# Gigabit_Ethernet.net
KiCad netlist of a schematic drawn in Altium Designer
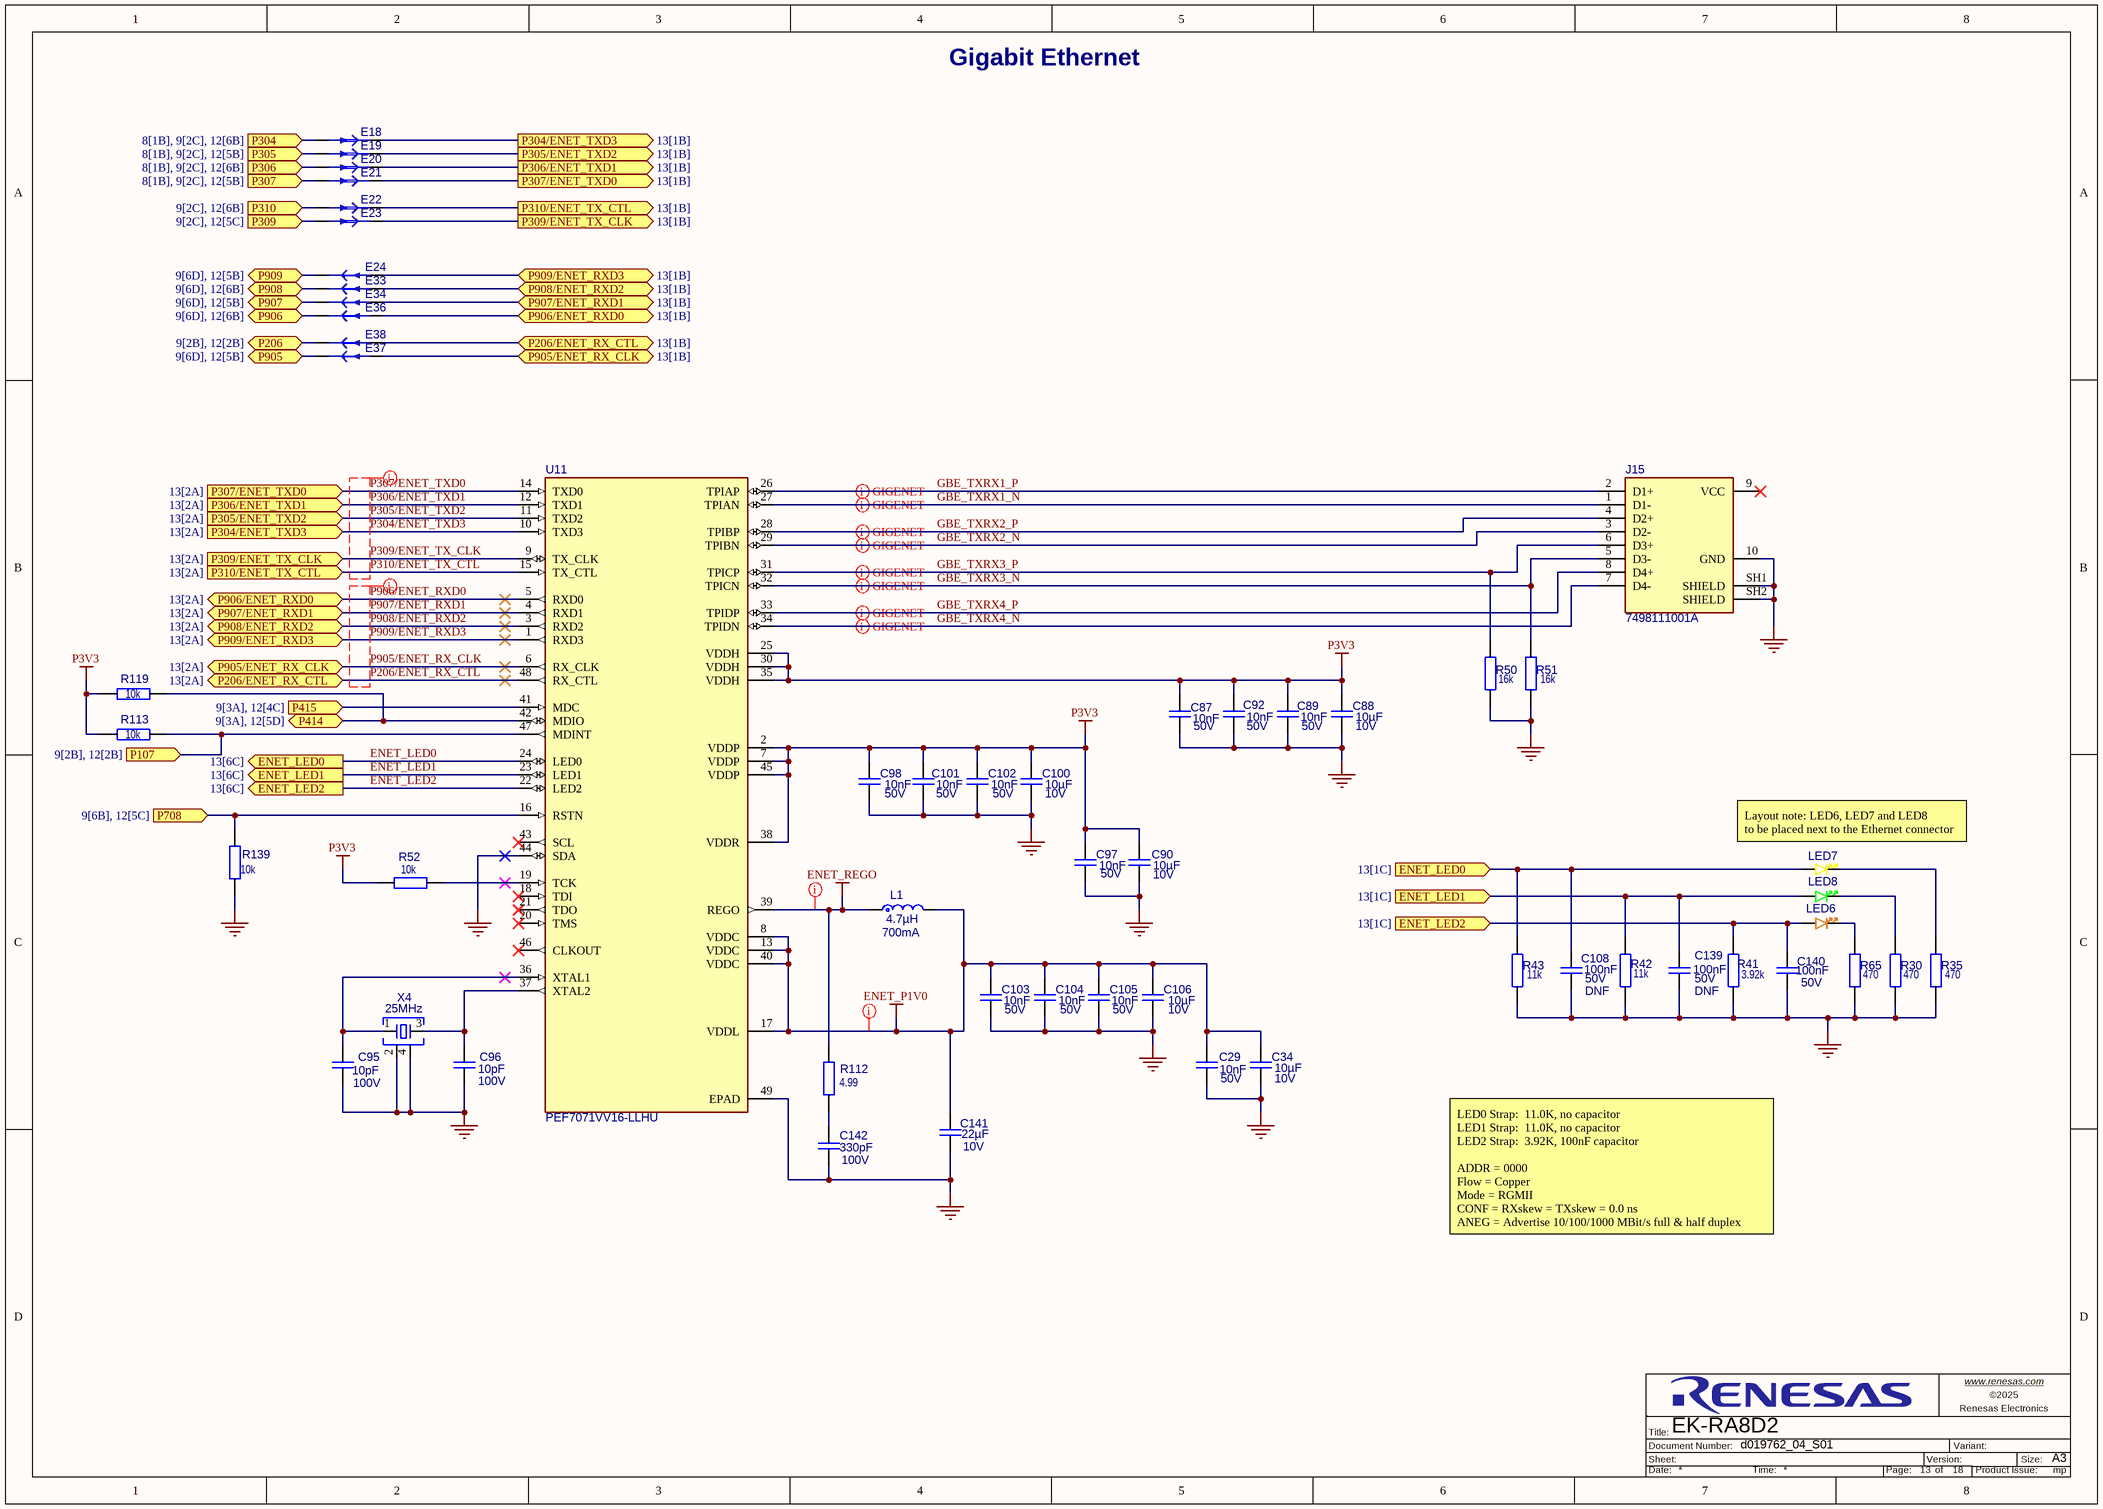
[diagram p0: Gigabit Ethernet.SchDoc]

(export (version "E")
  (design (tool "Eeschema 10.0.6"))
  (components
    (comp (ref "C29")
      (value "10nF")
      (footprint "C_EIA0402_0p55")
      (description "Capacitor,EIA0402,10n,50V,X7R")
      (fields
        (field (name "TOLERANCE") "10%")
        (field (name "OPERATING VOLTAGE MAX") "50V")
        (field (name "Comment") "Capacitor")
      )
      (libsource (lib "ek-ra8d2_mp - Customer") (part "Capacitor"))
    )
    (comp (ref "C34")
      (value "10µF")
      (footprint "C_EIA0402_0p7")
      (description "Capacitor,EIA0402,10u,10V,X5R")
      (fields
        (field (name "TOLERANCE") "20%")
        (field (name "OPERATING VOLTAGE MAX") "10V")
        (field (name "Comment") "Capacitor")
      )
      (libsource (lib "ek-ra8d2_mp - Customer") (part "Capacitor"))
    )
    (comp (ref "C87")
      (value "10nF")
      (footprint "C_EIA0402_0p55")
      (description "Capacitor,EIA0402,10n,50V,X7R")
      (fields
        (field (name "TOLERANCE") "10%")
        (field (name "OPERATING VOLTAGE MAX") "50V")
        (field (name "Comment") "Capacitor")
      )
      (libsource (lib "ek-ra8d2_mp - Customer") (part "Capacitor"))
    )
    (comp (ref "C88")
      (value "10µF")
      (footprint "C_EIA0402_0p7")
      (description "Capacitor,EIA0402,10u,10V,X5R")
      (fields
        (field (name "TOLERANCE") "20%")
        (field (name "OPERATING VOLTAGE MAX") "10V")
        (field (name "Comment") "Capacitor")
      )
      (libsource (lib "ek-ra8d2_mp - Customer") (part "Capacitor"))
    )
    (comp (ref "C89")
      (value "10nF")
      (footprint "C_EIA0402_0p55")
      (description "Capacitor,EIA0402,10n,50V,X7R")
      (fields
        (field (name "TOLERANCE") "10%")
        (field (name "OPERATING VOLTAGE MAX") "50V")
        (field (name "Comment") "Capacitor")
      )
      (libsource (lib "ek-ra8d2_mp - Customer") (part "Capacitor"))
    )
    (comp (ref "C90")
      (value "10µF")
      (footprint "C_EIA0402_0p7")
      (description "Capacitor,EIA0402,10u,10V,X5R")
      (fields
        (field (name "TOLERANCE") "20%")
        (field (name "OPERATING VOLTAGE MAX") "10V")
        (field (name "Comment") "Capacitor")
      )
      (libsource (lib "ek-ra8d2_mp - Customer") (part "Capacitor"))
    )
    (comp (ref "C92")
      (value "10nF")
      (footprint "C_EIA0402_0p55")
      (description "Capacitor,EIA0402,10n,50V,X7R")
      (fields
        (field (name "TOLERANCE") "10%")
        (field (name "OPERATING VOLTAGE MAX") "50V")
        (field (name "Comment") "Capacitor")
      )
      (libsource (lib "ek-ra8d2_mp - Customer") (part "Capacitor"))
    )
    (comp (ref "C95")
      (value "10pF")
      (footprint "C_EIA0402_0p55")
      (description "Capacitor,EIA0402,10p,100V,C0G")
      (fields
        (field (name "TOLERANCE") "5%")
        (field (name "OPERATING VOLTAGE MAX") "100V")
        (field (name "Comment") "Capacitor")
      )
      (libsource (lib "ek-ra8d2_mp - Customer") (part "Capacitor"))
    )
    (comp (ref "C96")
      (value "10pF")
      (footprint "C_EIA0402_0p55")
      (description "Capacitor,EIA0402,10p,100V,C0G")
      (fields
        (field (name "TOLERANCE") "5%")
        (field (name "OPERATING VOLTAGE MAX") "100V")
        (field (name "Comment") "Capacitor")
      )
      (libsource (lib "ek-ra8d2_mp - Customer") (part "Capacitor"))
    )
    (comp (ref "C97")
      (value "10nF")
      (footprint "C_EIA0402_0p55")
      (description "Capacitor,EIA0402,10n,50V,X7R")
      (fields
        (field (name "TOLERANCE") "10%")
        (field (name "OPERATING VOLTAGE MAX") "50V")
        (field (name "Comment") "Capacitor")
      )
      (libsource (lib "ek-ra8d2_mp - Customer") (part "Capacitor"))
    )
    (comp (ref "C98")
      (value "10nF")
      (footprint "C_EIA0402_0p55")
      (description "Capacitor,EIA0402,10n,50V,X7R")
      (fields
        (field (name "TOLERANCE") "10%")
        (field (name "OPERATING VOLTAGE MAX") "50V")
        (field (name "Comment") "Capacitor")
      )
      (libsource (lib "ek-ra8d2_mp - Customer") (part "Capacitor"))
    )
    (comp (ref "C100")
      (value "10µF")
      (footprint "C_EIA0402_0p7")
      (description "Capacitor,EIA0402,10u,10V,X5R")
      (fields
        (field (name "TOLERANCE") "20%")
        (field (name "OPERATING VOLTAGE MAX") "10V")
        (field (name "Comment") "Capacitor")
      )
      (libsource (lib "ek-ra8d2_mp - Customer") (part "Capacitor"))
    )
    (comp (ref "C101")
      (value "10nF")
      (footprint "C_EIA0402_0p55")
      (description "Capacitor,EIA0402,10n,50V,X7R")
      (fields
        (field (name "TOLERANCE") "10%")
        (field (name "OPERATING VOLTAGE MAX") "50V")
        (field (name "Comment") "Capacitor")
      )
      (libsource (lib "ek-ra8d2_mp - Customer") (part "Capacitor"))
    )
    (comp (ref "C102")
      (value "10nF")
      (footprint "C_EIA0402_0p55")
      (description "Capacitor,EIA0402,10n,50V,X7R")
      (fields
        (field (name "TOLERANCE") "10%")
        (field (name "OPERATING VOLTAGE MAX") "50V")
        (field (name "Comment") "Capacitor")
      )
      (libsource (lib "ek-ra8d2_mp - Customer") (part "Capacitor"))
    )
    (comp (ref "C103")
      (value "10nF")
      (footprint "C_EIA0402_0p55")
      (description "Capacitor,EIA0402,10n,50V,X7R")
      (fields
        (field (name "TOLERANCE") "10%")
        (field (name "OPERATING VOLTAGE MAX") "50V")
        (field (name "Comment") "Capacitor")
      )
      (libsource (lib "ek-ra8d2_mp - Customer") (part "Capacitor"))
    )
    (comp (ref "C104")
      (value "10nF")
      (footprint "C_EIA0402_0p55")
      (description "Capacitor,EIA0402,10n,50V,X7R")
      (fields
        (field (name "TOLERANCE") "10%")
        (field (name "OPERATING VOLTAGE MAX") "50V")
        (field (name "Comment") "Capacitor")
      )
      (libsource (lib "ek-ra8d2_mp - Customer") (part "Capacitor"))
    )
    (comp (ref "C105")
      (value "10nF")
      (footprint "C_EIA0402_0p55")
      (description "Capacitor,EIA0402,10n,50V,X7R")
      (fields
        (field (name "TOLERANCE") "10%")
        (field (name "OPERATING VOLTAGE MAX") "50V")
        (field (name "Comment") "Capacitor")
      )
      (libsource (lib "ek-ra8d2_mp - Customer") (part "Capacitor"))
    )
    (comp (ref "C106")
      (value "10µF")
      (footprint "C_EIA0402_0p7")
      (description "Capacitor,EIA0402,10u,10V,X5R")
      (fields
        (field (name "TOLERANCE") "20%")
        (field (name "OPERATING VOLTAGE MAX") "10V")
        (field (name "Comment") "Capacitor")
      )
      (libsource (lib "ek-ra8d2_mp - Customer") (part "Capacitor"))
    )
    (comp (ref "C108")
      (value "100nF")
      (footprint "C_EIA0402_0p55")
      (description "Capacitor,EIA0402,100n,50V,X7R")
      (fields
        (field (name "TOLERANCE") "10%")
        (field (name "OPERATING VOLTAGE MAX") "50V")
        (field (name "DNF") "DNF")
        (field (name "Comment") "Capacitor")
      )
      (libsource (lib "ek-ra8d2_mp - Customer") (part "Capacitor"))
    )
    (comp (ref "C139")
      (value "100nF")
      (footprint "C_EIA0402_0p55")
      (description "Capacitor,EIA0402,100n,50V,X7R")
      (fields
        (field (name "TOLERANCE") "10%")
        (field (name "OPERATING VOLTAGE MAX") "50V")
        (field (name "DNF") "DNF")
        (field (name "Comment") "Capacitor")
      )
      (libsource (lib "ek-ra8d2_mp - Customer") (part "Capacitor"))
    )
    (comp (ref "C140")
      (value "100nF")
      (footprint "C_EIA0402_0p55")
      (description "Capacitor,EIA0402,100n,50V,X7R")
      (fields
        (field (name "TOLERANCE") "10%")
        (field (name "OPERATING VOLTAGE MAX") "50V")
        (field (name "Comment") "Capacitor")
      )
      (libsource (lib "ek-ra8d2_mp - Customer") (part "Capacitor"))
    )
    (comp (ref "C141")
      (value "22µF")
      (footprint "C_EIA0402_0p9")
      (description "Capacitor,EIA0402,22u,10V,X5R")
      (fields
        (field (name "TOLERANCE") "20%")
        (field (name "OPERATING VOLTAGE MAX") "10V")
        (field (name "Comment") "Capacitor")
      )
      (libsource (lib "ek-ra8d2_mp - Customer") (part "Capacitor"))
    )
    (comp (ref "C142")
      (value "330pF")
      (footprint "C_EIA0402_0p55")
      (description "Capacitor,EIA0402,330p,100V,X7R")
      (fields
        (field (name "TOLERANCE") "10%")
        (field (name "OPERATING VOLTAGE MAX") "100V")
        (field (name "Comment") "GCM155R72A331KA37D")
      )
      (libsource (lib "ek-ra8d2_mp - Customer") (part "Capacitor"))
    )
    (comp (ref "E18")
      (value "TRACE_CUT_0805")
      (footprint "trace_cut_0805")
      (description "Trace Cut, SMD, 0805 size")
      (libsource (lib "ek-ra8d2_mp - Customer") (part "trace_cut"))
    )
    (comp (ref "E19")
      (value "TRACE_CUT_0805")
      (footprint "trace_cut_0805")
      (description "Trace Cut, SMD, 0805 size")
      (libsource (lib "ek-ra8d2_mp - Customer") (part "trace_cut"))
    )
    (comp (ref "E20")
      (value "TRACE_CUT_0805")
      (footprint "trace_cut_0805")
      (description "Trace Cut, SMD, 0805 size")
      (libsource (lib "ek-ra8d2_mp - Customer") (part "trace_cut"))
    )
    (comp (ref "E21")
      (value "TRACE_CUT_0805")
      (footprint "trace_cut_0805")
      (description "Trace Cut, SMD, 0805 size")
      (libsource (lib "ek-ra8d2_mp - Customer") (part "trace_cut"))
    )
    (comp (ref "E22")
      (value "TRACE_CUT_0805")
      (footprint "trace_cut_0805")
      (description "Trace Cut, SMD, 0805 size")
      (libsource (lib "ek-ra8d2_mp - Customer") (part "trace_cut"))
    )
    (comp (ref "E23")
      (value "TRACE_CUT_0805")
      (footprint "trace_cut_0805")
      (description "Trace Cut, SMD, 0805 size")
      (libsource (lib "ek-ra8d2_mp - Customer") (part "trace_cut"))
    )
    (comp (ref "E24")
      (value "TRACE_CUT_0805")
      (footprint "trace_cut_0805")
      (description "Trace Cut, SMD, 0805 size")
      (libsource (lib "ek-ra8d2_mp - Customer") (part "trace_cut"))
    )
    (comp (ref "E33")
      (value "TRACE_CUT_0805")
      (footprint "trace_cut_0805")
      (description "Trace Cut, SMD, 0805 size")
      (libsource (lib "ek-ra8d2_mp - Customer") (part "trace_cut"))
    )
    (comp (ref "E34")
      (value "TRACE_CUT_0805")
      (footprint "trace_cut_0805")
      (description "Trace Cut, SMD, 0805 size")
      (libsource (lib "ek-ra8d2_mp - Customer") (part "trace_cut"))
    )
    (comp (ref "E36")
      (value "TRACE_CUT_0805")
      (footprint "trace_cut_0805")
      (description "Trace Cut, SMD, 0805 size")
      (libsource (lib "ek-ra8d2_mp - Customer") (part "trace_cut"))
    )
    (comp (ref "E37")
      (value "TRACE_CUT_0805")
      (footprint "trace_cut_0805")
      (description "Trace Cut, SMD, 0805 size")
      (libsource (lib "ek-ra8d2_mp - Customer") (part "trace_cut"))
    )
    (comp (ref "E38")
      (value "TRACE_CUT_0805")
      (footprint "trace_cut_0805")
      (description "Trace Cut, SMD, 0805 size")
      (libsource (lib "ek-ra8d2_mp - Customer") (part "trace_cut"))
    )
    (comp (ref "J15")
      (value "7498111001A")
      (footprint "wue_7498111001A")
      (description "10/100/1000 Ethernet Jack, RJ45, Right Angle SMT, No LEDs")
      (libsource (lib "ek-ra8d2_mp - Customer") (part "wue_7498111001A"))
    )
    (comp (ref "L1")
      (value "4.7µH")
      (footprint "L_EIA0805")
      (description "Power Inductor Shielded Multilayer 4.7uH 20% 3MHz Ferrite 700mA")
      (fields
        (field (name "TOLERANCE") "20%")
        (field (name "CURRENT") "700mA")
        (field (name "Comment") "Inductor")
      )
      (libsource (lib "ek-ra8d2_mp - Customer") (part "Inductor"))
    )
    (comp (ref "LED6")
      (value "LO L29K-H2L1-24")
      (footprint "led_0603_o")
      (description "Standard LEDs - SMD Orange, 606nm 3.55 to 14 mcd")
      (libsource (lib "ek-ra8d2_mp - Customer") (part "LED_orange"))
    )
    (comp (ref "LED7")
      (value "150060YS75000")
      (footprint "led_0603_y")
      (description "Standard LEDs - SMD Yellow, 590nm 90 to 120 mcd")
      (libsource (lib "ek-ra8d2_mp - Customer") (part "LED_yellow"))
    )
    (comp (ref "LED8")
      (value "LG L29K-G2J1-24")
      (footprint "led_0603_g")
      (description "Standard LEDs - SMD Green, 570nm 2.2 to 5.6 mcd")
      (libsource (lib "ek-ra8d2_mp - Customer") (part "LED_green"))
    )
    (comp (ref "R30")
      (value "470")
      (footprint "R_EIA0402")
      (description "Resistor,EIA0402,470,0.0625W")
      (fields (field (name "POWER") "62.5mW") (field (name "TOLERANCE") "1%"))
      (libsource (lib "ek-ra8d2_mp - Customer") (part "Resistor"))
    )
    (comp (ref "R35")
      (value "470")
      (footprint "R_EIA0402")
      (description "Resistor,EIA0402,470,0.0625W")
      (fields (field (name "POWER") "62.5mW") (field (name "TOLERANCE") "1%"))
      (libsource (lib "ek-ra8d2_mp - Customer") (part "Resistor"))
    )
    (comp (ref "R41")
      (value "3.92k")
      (footprint "R_EIA0402")
      (description "Resistor,EIA0402,3.92k,0.0625W")
      (fields (field (name "POWER") "62.5mW") (field (name "TOLERANCE") "1%"))
      (libsource (lib "ek-ra8d2_mp - Customer") (part "Resistor"))
    )
    (comp (ref "R42")
      (value "11k")
      (footprint "R_EIA0402")
      (description "Resistor,EIA0402,11k,0.0625W")
      (fields (field (name "POWER") "62.5mW") (field (name "TOLERANCE") "1%"))
      (libsource (lib "ek-ra8d2_mp - Customer") (part "Resistor"))
    )
    (comp (ref "R43")
      (value "11k")
      (footprint "R_EIA0402")
      (description "Resistor,EIA0402,11k,0.0625W")
      (fields (field (name "POWER") "62.5mW") (field (name "TOLERANCE") "1%"))
      (libsource (lib "ek-ra8d2_mp - Customer") (part "Resistor"))
    )
    (comp (ref "R50")
      (value "16k")
      (footprint "R_EIA0402")
      (description "Resistor,EIA0402,16k,0.0625W")
      (fields (field (name "POWER") "62.5mW") (field (name "TOLERANCE") "1%"))
      (libsource (lib "ek-ra8d2_mp - Customer") (part "Resistor"))
    )
    (comp (ref "R51")
      (value "16k")
      (footprint "R_EIA0402")
      (description "Resistor,EIA0402,16k,0.0625W")
      (fields (field (name "POWER") "62.5mW") (field (name "TOLERANCE") "1%"))
      (libsource (lib "ek-ra8d2_mp - Customer") (part "Resistor"))
    )
    (comp (ref "R52")
      (value "10k")
      (footprint "R_EIA0402")
      (description "Resistor,EIA0402,10k,0.0625W")
      (fields (field (name "POWER") "62.5mW") (field (name "TOLERANCE") "1%"))
      (libsource (lib "") (part "Resistor_1"))
    )
    (comp (ref "R65")
      (value "470")
      (footprint "R_EIA0402")
      (description "Resistor,EIA0402,470,0.0625W")
      (fields (field (name "POWER") "62.5mW") (field (name "TOLERANCE") "1%"))
      (libsource (lib "ek-ra8d2_mp - Customer") (part "Resistor"))
    )
    (comp (ref "R112")
      (value "4.99")
      (footprint "R_EIA0402")
      (description "Resistor,EIA0402,4.99,0.0625W")
      (fields (field (name "POWER") "62.5mW") (field (name "TOLERANCE") "1%"))
      (libsource (lib "ek-ra8d2_mp - Customer") (part "Resistor"))
    )
    (comp (ref "R113")
      (value "10k")
      (footprint "R_EIA0402")
      (description "Resistor,EIA0402,10k,0.0625W")
      (fields (field (name "POWER") "62.5mW") (field (name "TOLERANCE") "1%"))
      (libsource (lib "") (part "Resistor_1"))
    )
    (comp (ref "R119")
      (value "10k")
      (footprint "R_EIA0402")
      (description "Resistor,EIA0402,10k,0.0625W")
      (fields (field (name "POWER") "62.5mW") (field (name "TOLERANCE") "1%"))
      (libsource (lib "") (part "Resistor_1"))
    )
    (comp (ref "R139")
      (value "10k")
      (footprint "R_EIA0402")
      (description "Resistor,EIA0402,10k,0.0625W")
      (fields (field (name "POWER") "62.5mW") (field (name "TOLERANCE") "1%"))
      (libsource (lib "ek-ra8d2_mp - Customer") (part "Resistor"))
    )
    (comp (ref "U11")
      (value "PEF7071VV16-LLHU")
      (footprint "mxl_PG-VQFN-48_7x7")
      (description "Ethernet Network Connection GPY111 Gigabit Ethernet (GbE)")
      (libsource (lib "ek-ra8d2_mp - Customer") (part "mxl_PEF7071VV16"))
    )
    (comp (ref "X4")
      (value "25MHz")
      (footprint "ecs-ECX-1637B")
      (description "Crystal, 25.000MHz, 10 pF, 2x1.6")
      (fields (field (name "TOLERANCE") "10ppm") (field (name "Comment") "ECS-250-10-37B-CTN-TR"))
      (libsource (lib "ek-ra8d2_mp - Customer") (part "Crystal_4pin"))
    )
  )
  (nets
    (net (code "1") (name "/ENET_LED0") (class "Default")
      (node (ref "C108") (pin "1") (pinfunction "1_1") (pintype "passive"))
      (node (ref "LED7") (pin "2") (pinfunction "A_2") (pintype "passive"))
      (node (ref "R43") (pin "2") (pinfunction "2_2") (pintype "passive"))
      (node (ref "U11") (pin "24") (pinfunction "LED0_24") (pintype "bidirectional"))
    )
    (net (code "2") (name "/ENET_LED1") (class "Default")
      (node (ref "C139") (pin "1") (pinfunction "1_1") (pintype "passive"))
      (node (ref "LED8") (pin "2") (pinfunction "A_2") (pintype "passive"))
      (node (ref "R42") (pin "2") (pinfunction "2_2") (pintype "passive"))
      (node (ref "U11") (pin "23") (pinfunction "LED1_23") (pintype "bidirectional"))
    )
    (net (code "3") (name "/ENET_LED2") (class "Default")
      (node (ref "C140") (pin "1") (pinfunction "1_1") (pintype "passive"))
      (node (ref "LED6") (pin "2") (pinfunction "A_2") (pintype "passive"))
      (node (ref "R41") (pin "2") (pinfunction "2_2") (pintype "passive"))
      (node (ref "U11") (pin "22") (pinfunction "LED2_22") (pintype "bidirectional"))
    )
    (net (code "4") (name "/GBE_TXRX1_N") (class "Default")
      (node (ref "J15") (pin "1") (pinfunction "D1-_1") (pintype "passive"))
      (node (ref "U11") (pin "27") (pinfunction "TPIAN_27") (pintype "bidirectional"))
    )
    (net (code "5") (name "/GBE_TXRX1_P") (class "Default")
      (node (ref "J15") (pin "2") (pinfunction "D1+_2") (pintype "passive"))
      (node (ref "U11") (pin "26") (pinfunction "TPIAP_26") (pintype "bidirectional"))
    )
    (net (code "6") (name "/GBE_TXRX2_N") (class "Default")
      (node (ref "J15") (pin "3") (pinfunction "D2-_3") (pintype "passive"))
      (node (ref "U11") (pin "29") (pinfunction "TPIBN_29") (pintype "bidirectional"))
    )
    (net (code "7") (name "/GBE_TXRX2_P") (class "Default")
      (node (ref "J15") (pin "4") (pinfunction "D2+_4") (pintype "passive"))
      (node (ref "U11") (pin "28") (pinfunction "TPIBP_28") (pintype "bidirectional"))
    )
    (net (code "8") (name "/GBE_TXRX3_N") (class "Default")
      (node (ref "J15") (pin "5") (pinfunction "D3-_5") (pintype "passive"))
      (node (ref "R51") (pin "2") (pinfunction "2_2") (pintype "passive"))
      (node (ref "U11") (pin "32") (pinfunction "TPICN_32") (pintype "bidirectional"))
    )
    (net (code "9") (name "/GBE_TXRX3_P") (class "Default")
      (node (ref "J15") (pin "6") (pinfunction "D3+_6") (pintype "passive"))
      (node (ref "R50") (pin "2") (pinfunction "2_2") (pintype "passive"))
      (node (ref "U11") (pin "31") (pinfunction "TPICP_31") (pintype "bidirectional"))
    )
    (net (code "10") (name "/GBE_TXRX4_N") (class "Default")
      (node (ref "J15") (pin "7") (pinfunction "D4-_7") (pintype "passive"))
      (node (ref "U11") (pin "34") (pinfunction "TPIDN_34") (pintype "bidirectional"))
    )
    (net (code "11") (name "/GBE_TXRX4_P") (class "Default")
      (node (ref "J15") (pin "8") (pinfunction "D4+_8") (pintype "passive"))
      (node (ref "U11") (pin "33") (pinfunction "TPIDP_33") (pintype "bidirectional"))
    )
    (net (code "12") (name "/P107") (class "Default")
      (node (ref "R113") (pin "2") (pinfunction "2_2") (pintype "passive"))
      (node (ref "U11") (pin "47") (pinfunction "MDINT_47") (pintype "output"))
    )
    (net (code "13") (name "/P206") (class "Default")
      (node (ref "E38") (pin "1") (pinfunction "1_1") (pintype "passive"))
    )
    (net (code "14") (name "/P206{slash}ENET_RX_CTL") (class "Default")
      (node (ref "E38") (pin "2") (pinfunction "2_2") (pintype "passive"))
      (node (ref "U11") (pin "48") (pinfunction "RX_CTL_48") (pintype "output"))
    )
    (net (code "15") (name "/P304") (class "Default")
      (node (ref "E18") (pin "2") (pinfunction "2_2") (pintype "passive"))
    )
    (net (code "16") (name "/P304{slash}ENET_TXD3") (class "Default")
      (node (ref "E18") (pin "1") (pinfunction "1_1") (pintype "passive"))
      (node (ref "U11") (pin "10") (pinfunction "TXD3_10") (pintype "input"))
    )
    (net (code "17") (name "/P305") (class "Default")
      (node (ref "E19") (pin "2") (pinfunction "2_2") (pintype "passive"))
    )
    (net (code "18") (name "/P305{slash}ENET_TXD2") (class "Default")
      (node (ref "E19") (pin "1") (pinfunction "1_1") (pintype "passive"))
      (node (ref "U11") (pin "11") (pinfunction "TXD2_11") (pintype "input"))
    )
    (net (code "19") (name "/P306") (class "Default")
      (node (ref "E20") (pin "2") (pinfunction "2_2") (pintype "passive"))
    )
    (net (code "20") (name "/P306{slash}ENET_TXD1") (class "Default")
      (node (ref "E20") (pin "1") (pinfunction "1_1") (pintype "passive"))
      (node (ref "U11") (pin "12") (pinfunction "TXD1_12") (pintype "input"))
    )
    (net (code "21") (name "/P307") (class "Default")
      (node (ref "E21") (pin "2") (pinfunction "2_2") (pintype "passive"))
    )
    (net (code "22") (name "/P307{slash}ENET_TXD0") (class "Default")
      (node (ref "E21") (pin "1") (pinfunction "1_1") (pintype "passive"))
      (node (ref "U11") (pin "14") (pinfunction "TXD0_14") (pintype "input"))
    )
    (net (code "23") (name "/P309") (class "Default")
      (node (ref "E23") (pin "2") (pinfunction "2_2") (pintype "passive"))
    )
    (net (code "24") (name "/P309{slash}ENET_TX_CLK") (class "Default")
      (node (ref "E23") (pin "1") (pinfunction "1_1") (pintype "passive"))
      (node (ref "U11") (pin "9") (pinfunction "TX_CLK_9") (pintype "bidirectional"))
    )
    (net (code "25") (name "/P310") (class "Default")
      (node (ref "E22") (pin "2") (pinfunction "2_2") (pintype "passive"))
    )
    (net (code "26") (name "/P310{slash}ENET_TX_CTL") (class "Default")
      (node (ref "E22") (pin "1") (pinfunction "1_1") (pintype "passive"))
      (node (ref "U11") (pin "15") (pinfunction "TX_CTL_15") (pintype "input"))
    )
    (net (code "27") (name "/P414") (class "Default")
      (node (ref "R119") (pin "2") (pinfunction "2_2") (pintype "passive"))
      (node (ref "U11") (pin "42") (pinfunction "MDIO_42") (pintype "bidirectional"))
    )
    (net (code "28") (name "/P415") (class "Default")
      (node (ref "U11") (pin "41") (pinfunction "MDC_41") (pintype "input"))
    )
    (net (code "29") (name "/P708") (class "Default")
      (node (ref "R139") (pin "2") (pinfunction "2_2") (pintype "passive"))
      (node (ref "U11") (pin "16") (pinfunction "RSTN_16") (pintype "input"))
    )
    (net (code "30") (name "/P905") (class "Default")
      (node (ref "E37") (pin "1") (pinfunction "1_1") (pintype "passive"))
    )
    (net (code "31") (name "/P905{slash}ENET_RX_CLK") (class "Default")
      (node (ref "E37") (pin "2") (pinfunction "2_2") (pintype "passive"))
      (node (ref "U11") (pin "6") (pinfunction "RX_CLK_6") (pintype "output"))
    )
    (net (code "32") (name "/P906") (class "Default")
      (node (ref "E36") (pin "1") (pinfunction "1_1") (pintype "passive"))
    )
    (net (code "33") (name "/P906{slash}ENET_RXD0") (class "Default")
      (node (ref "E36") (pin "2") (pinfunction "2_2") (pintype "passive"))
      (node (ref "U11") (pin "5") (pinfunction "RXD0_5") (pintype "output"))
    )
    (net (code "34") (name "/P907") (class "Default")
      (node (ref "E34") (pin "1") (pinfunction "1_1") (pintype "passive"))
    )
    (net (code "35") (name "/P907{slash}ENET_RXD1") (class "Default")
      (node (ref "E34") (pin "2") (pinfunction "2_2") (pintype "passive"))
      (node (ref "U11") (pin "4") (pinfunction "RXD1_4") (pintype "output"))
    )
    (net (code "36") (name "/P908") (class "Default")
      (node (ref "E33") (pin "1") (pinfunction "1_1") (pintype "passive"))
    )
    (net (code "37") (name "/P908{slash}ENET_RXD2") (class "Default")
      (node (ref "E33") (pin "2") (pinfunction "2_2") (pintype "passive"))
      (node (ref "U11") (pin "3") (pinfunction "RXD2_3") (pintype "output"))
    )
    (net (code "38") (name "/P909") (class "Default")
      (node (ref "E24") (pin "1") (pinfunction "1_1") (pintype "passive"))
    )
    (net (code "39") (name "/P909{slash}ENET_RXD3") (class "Default")
      (node (ref "E24") (pin "2") (pinfunction "2_2") (pintype "passive"))
      (node (ref "U11") (pin "1") (pinfunction "RXD3_1") (pintype "output"))
    )
    (net (code "40") (name "ENET_P1V0") (class "Default")
      (node (ref "C103") (pin "1") (pinfunction "1_1") (pintype "passive"))
      (node (ref "C104") (pin "1") (pinfunction "1_1") (pintype "passive"))
      (node (ref "C105") (pin "1") (pinfunction "1_1") (pintype "passive"))
      (node (ref "C106") (pin "1") (pinfunction "1_1") (pintype "passive"))
      (node (ref "C141") (pin "2") (pinfunction "2_2") (pintype "passive"))
      (node (ref "C29") (pin "1") (pinfunction "1_1") (pintype "passive"))
      (node (ref "C34") (pin "1") (pinfunction "1_1") (pintype "passive"))
      (node (ref "L1") (pin "2") (pinfunction "2_2") (pintype "passive"))
      (node (ref "U11") (pin "13") (pinfunction "VDDC_13") (pintype "power_in"))
      (node (ref "U11") (pin "17") (pinfunction "VDDL_17") (pintype "power_in"))
      (node (ref "U11") (pin "40") (pinfunction "VDDC_40") (pintype "power_in"))
      (node (ref "U11") (pin "8") (pinfunction "VDDC_8") (pintype "power_in"))
    )
    (net (code "41") (name "ENET_REGO") (class "Default")
      (node (ref "L1") (pin "1") (pinfunction "1_1") (pintype "passive"))
      (node (ref "R112") (pin "2") (pinfunction "2_2") (pintype "passive"))
      (node (ref "U11") (pin "39") (pinfunction "REGO_39") (pintype "output"))
    )
    (net (code "42") (name "GND") (class "Default")
      (node (ref "C100") (pin "2") (pinfunction "2_2") (pintype "passive"))
      (node (ref "C101") (pin "2") (pinfunction "2_2") (pintype "passive"))
      (node (ref "C102") (pin "2") (pinfunction "2_2") (pintype "passive"))
      (node (ref "C103") (pin "2") (pinfunction "2_2") (pintype "passive"))
      (node (ref "C104") (pin "2") (pinfunction "2_2") (pintype "passive"))
      (node (ref "C105") (pin "2") (pinfunction "2_2") (pintype "passive"))
      (node (ref "C106") (pin "2") (pinfunction "2_2") (pintype "passive"))
      (node (ref "C108") (pin "2") (pinfunction "2_2") (pintype "passive"))
      (node (ref "C139") (pin "2") (pinfunction "2_2") (pintype "passive"))
      (node (ref "C140") (pin "2") (pinfunction "2_2") (pintype "passive"))
      (node (ref "C141") (pin "1") (pinfunction "1_1") (pintype "passive"))
      (node (ref "C142") (pin "1") (pinfunction "1_1") (pintype "passive"))
      (node (ref "C29") (pin "2") (pinfunction "2_2") (pintype "passive"))
      (node (ref "C34") (pin "2") (pinfunction "2_2") (pintype "passive"))
      (node (ref "C87") (pin "2") (pinfunction "2_2") (pintype "passive"))
      (node (ref "C88") (pin "2") (pinfunction "2_2") (pintype "passive"))
      (node (ref "C89") (pin "2") (pinfunction "2_2") (pintype "passive"))
      (node (ref "C90") (pin "2") (pinfunction "2_2") (pintype "passive"))
      (node (ref "C92") (pin "2") (pinfunction "2_2") (pintype "passive"))
      (node (ref "C95") (pin "1") (pinfunction "1_1") (pintype "passive"))
      (node (ref "C96") (pin "2") (pinfunction "2_2") (pintype "passive"))
      (node (ref "C97") (pin "2") (pinfunction "2_2") (pintype "passive"))
      (node (ref "C98") (pin "2") (pinfunction "2_2") (pintype "passive"))
      (node (ref "J15") (pin "10") (pinfunction "GND_10") (pintype "passive"))
      (node (ref "J15") (pin "SH1") (pinfunction "SHIELD_SH1") (pintype "power_in"))
      (node (ref "J15") (pin "SH2") (pinfunction "SHIELD_SH2") (pintype "power_in"))
      (node (ref "R139") (pin "1") (pinfunction "1_1") (pintype "passive"))
      (node (ref "R30") (pin "1") (pinfunction "1_1") (pintype "passive"))
      (node (ref "R35") (pin "1") (pinfunction "1_1") (pintype "passive"))
      (node (ref "R41") (pin "1") (pinfunction "1_1") (pintype "passive"))
      (node (ref "R42") (pin "1") (pinfunction "1_1") (pintype "passive"))
      (node (ref "R43") (pin "1") (pinfunction "1_1") (pintype "passive"))
      (node (ref "R50") (pin "1") (pinfunction "1_1") (pintype "passive"))
      (node (ref "R51") (pin "1") (pinfunction "1_1") (pintype "passive"))
      (node (ref "R65") (pin "1") (pinfunction "1_1") (pintype "passive"))
      (node (ref "U11") (pin "44") (pinfunction "SDA_44") (pintype "bidirectional"))
      (node (ref "U11") (pin "49") (pinfunction "EPAD_49") (pintype "power_in"))
      (node (ref "X4") (pin "2") (pinfunction "2_2") (pintype "passive"))
      (node (ref "X4") (pin "4") (pinfunction "4_4") (pintype "passive"))
    )
    (net (code "43") (name "Net-(C142-Pad2)") (class "Default")
      (node (ref "C142") (pin "2") (pinfunction "2_2") (pintype "passive"))
      (node (ref "R112") (pin "1") (pinfunction "1_1") (pintype "passive"))
    )
    (net (code "44") (name "Net-(LED6-K)") (class "Default")
      (node (ref "LED6") (pin "1") (pinfunction "K_1") (pintype "passive"))
      (node (ref "R65") (pin "2") (pinfunction "2_2") (pintype "passive"))
    )
    (net (code "45") (name "Net-(LED7-K)") (class "Default")
      (node (ref "LED7") (pin "1") (pinfunction "K_1") (pintype "passive"))
      (node (ref "R35") (pin "2") (pinfunction "2_2") (pintype "passive"))
    )
    (net (code "46") (name "Net-(LED8-K)") (class "Default")
      (node (ref "LED8") (pin "1") (pinfunction "K_1") (pintype "passive"))
      (node (ref "R30") (pin "2") (pinfunction "2_2") (pintype "passive"))
    )
    (net (code "47") (name "Net-(U11-TCK)") (class "Default")
      (node (ref "R52") (pin "2") (pinfunction "2_2") (pintype "passive"))
      (node (ref "U11") (pin "19") (pinfunction "TCK_19") (pintype "input"))
    )
    (net (code "48") (name "Net-(U11-XTAL1)") (class "Default")
      (node (ref "C95") (pin "2") (pinfunction "2_2") (pintype "passive"))
      (node (ref "U11") (pin "36") (pinfunction "XTAL1_36") (pintype "input"))
      (node (ref "X4") (pin "1") (pinfunction "1_1") (pintype "passive"))
    )
    (net (code "49") (name "Net-(U11-XTAL2)") (class "Default")
      (node (ref "C96") (pin "1") (pinfunction "1_1") (pintype "passive"))
      (node (ref "U11") (pin "37") (pinfunction "XTAL2_37") (pintype "output"))
      (node (ref "X4") (pin "3") (pinfunction "3_3") (pintype "passive"))
    )
    (net (code "50") (name "P3V3") (class "Default")
      (node (ref "C100") (pin "1") (pinfunction "1_1") (pintype "passive"))
      (node (ref "C101") (pin "1") (pinfunction "1_1") (pintype "passive"))
      (node (ref "C102") (pin "1") (pinfunction "1_1") (pintype "passive"))
      (node (ref "C87") (pin "1") (pinfunction "1_1") (pintype "passive"))
      (node (ref "C88") (pin "1") (pinfunction "1_1") (pintype "passive"))
      (node (ref "C89") (pin "1") (pinfunction "1_1") (pintype "passive"))
      (node (ref "C90") (pin "1") (pinfunction "1_1") (pintype "passive"))
      (node (ref "C92") (pin "1") (pinfunction "1_1") (pintype "passive"))
      (node (ref "C97") (pin "1") (pinfunction "1_1") (pintype "passive"))
      (node (ref "C98") (pin "1") (pinfunction "1_1") (pintype "passive"))
      (node (ref "R113") (pin "1") (pinfunction "1_1") (pintype "passive"))
      (node (ref "R119") (pin "1") (pinfunction "1_1") (pintype "passive"))
      (node (ref "R52") (pin "1") (pinfunction "1_1") (pintype "passive"))
      (node (ref "U11") (pin "2") (pinfunction "VDDP_2") (pintype "power_in"))
      (node (ref "U11") (pin "25") (pinfunction "VDDH_25") (pintype "power_in"))
      (node (ref "U11") (pin "30") (pinfunction "VDDH_30") (pintype "power_in"))
      (node (ref "U11") (pin "35") (pinfunction "VDDH_35") (pintype "power_in"))
      (node (ref "U11") (pin "38") (pinfunction "VDDR_38") (pintype "power_in"))
      (node (ref "U11") (pin "45") (pinfunction "VDDP_45") (pintype "power_in"))
      (node (ref "U11") (pin "7") (pinfunction "VDDP_7") (pintype "power_in"))
    )
    (net (code "51") (name "unconnected-(J15-VCC-Pad9)") (class "Default")
      (node (ref "J15") (pin "9") (pinfunction "VCC_9") (pintype "passive+no_connect"))
    )
    (net (code "52") (name "unconnected-(U11-CLKOUT-Pad46)") (class "Default")
      (node (ref "U11") (pin "46") (pinfunction "CLKOUT_46") (pintype "output+no_connect"))
    )
    (net (code "53") (name "unconnected-(U11-SCL-Pad43)") (class "Default")
      (node (ref "U11") (pin "43") (pinfunction "SCL_43") (pintype "output+no_connect"))
    )
    (net (code "54") (name "unconnected-(U11-TDI-Pad18)") (class "Default")
      (node (ref "U11") (pin "18") (pinfunction "TDI_18") (pintype "input+no_connect"))
    )
    (net (code "55") (name "unconnected-(U11-TDO-Pad21)") (class "Default")
      (node (ref "U11") (pin "21") (pinfunction "TDO_21") (pintype "output+no_connect"))
    )
    (net (code "56") (name "unconnected-(U11-TMS-Pad20)") (class "Default")
      (node (ref "U11") (pin "20") (pinfunction "TMS_20") (pintype "input+no_connect"))
    )
  )
)
